# usb.net
KiCad netlist of a schematic drawn in Altium Designer
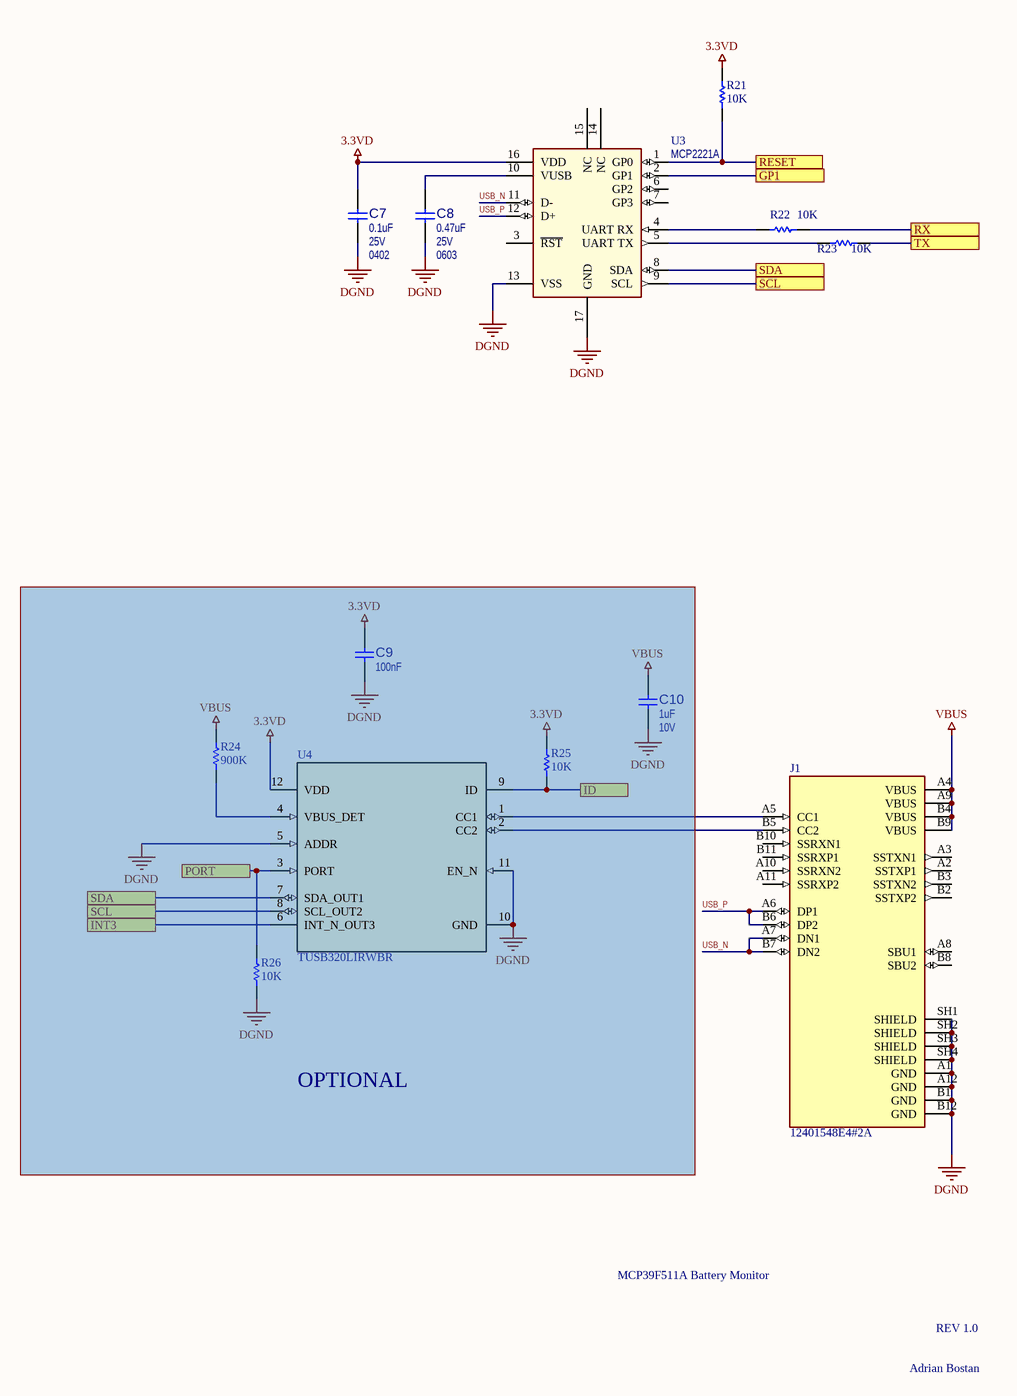
[diagram p0: usb.SchDoc]

(export (version "E")
  (design (tool "Eeschema 10.0.6"))
  (components
    (comp (ref "C7")
      (value "0.1uF")
      (footprint "CAP0603M")
      (description "Capacitor")
      (fields
        (field (name "VOLTAGE") "25V")
        (field (name "PACKAGE") "0402")
        (field (name "TOLERANCE") "10%")
        (field (name "OWNER") "Randolph Sobrepena")
      )
      (libsource (lib "MCHP-CDB") (part "Capacitor NP"))
    )
    (comp (ref "C8")
      (value "0.47uF")
      (footprint "CAP0603M")
      (description "Capacitor")
      (fields
        (field (name "VOLTAGE") "25V")
        (field (name "PACKAGE") "0603")
        (field (name "TOLERANCE") "10%")
        (field (name "OWNER") "Tad Ahlvers")
      )
      (libsource (lib "MCHP-CDB") (part "Capacitor NP"))
    )
    (comp (ref "C9")
      (value "100nF")
      (footprint "CAP0603M")
      (description "Capacitor")
      (fields (field (name "TOLERANCE") "10%") (field (name "OWNER") "Aaron VanDuerm"))
      (libsource (lib "MCHP-CDB") (part "Capacitor NP"))
    )
    (comp (ref "C10")
      (value "1uF")
      (footprint "CAP0603M")
      (description "Capacitor")
      (fields
        (field (name "VOLTAGE") "10V")
        (field (name "TOLERANCE") "10%")
        (field (name "OWNER") "Aaron VanDuerm")
      )
      (libsource (lib "MCHP-CDB") (part "Capacitor NP"))
    )
    (comp (ref "J1")
      (value "12401548E4#2A")
      (footprint "12401548E4#2A")
      (fields (field (name "MF") "Amphenol ICC"))
      (libsource (lib "12401548E4_2A") (part "12401548E4#2A"))
    )
    (comp (ref "R21")
      (value "10K")
      (footprint "RES0603M")
      (description "Resistor")
      (fields (field (name "Comment") "Res1") (field (name "PUBLISHER") "Altium Limited"))
      (libsource (lib "Miscellaneous Devices") (part "Res1"))
    )
    (comp (ref "R22")
      (value "10K")
      (footprint "RES0603M")
      (description "Resistor")
      (fields (field (name "Comment") "Res1") (field (name "PUBLISHER") "Altium Limited"))
      (libsource (lib "Miscellaneous Devices") (part "Res1"))
    )
    (comp (ref "R23")
      (value "10K")
      (footprint "RES0603M")
      (description "Resistor")
      (fields (field (name "Comment") "Res1") (field (name "PUBLISHER") "Altium Limited"))
      (libsource (lib "Miscellaneous Devices") (part "Res1"))
    )
    (comp (ref "R24")
      (value "900K")
      (footprint "RES0603M")
      (description "Resistor")
      (fields (field (name "Comment") "Res1") (field (name "PUBLISHER") "Altium Limited"))
      (libsource (lib "Miscellaneous Devices") (part "Res1"))
    )
    (comp (ref "R25")
      (value "10K")
      (footprint "RES0603M")
      (description "Resistor")
      (fields (field (name "Comment") "Res1") (field (name "PUBLISHER") "Altium Limited"))
      (libsource (lib "Miscellaneous Devices") (part "Res1"))
    )
    (comp (ref "R26")
      (value "10K")
      (footprint "RES0603M")
      (description "Resistor")
      (fields (field (name "Comment") "Res1") (field (name "PUBLISHER") "Altium Limited"))
      (libsource (lib "Miscellaneous Devices") (part "Res1"))
    )
    (comp (ref "U3")
      (value "MCP2221A")
      (footprint "QFN65P400X400X95-17N")
      (fields (field (name "Comment") "MCP2221") (field (name "OWNER") "Tim Moffat"))
      (libsource (lib "MCP2221A") (part "MCP2221"))
    )
    (comp (ref "U4")
      (value "TUSB320LIRWBR")
      (footprint "12-x2qfn")
      (description "Imported")
      (fields (field (name "MANUFACTURER") "Texas Instruments"))
      (libsource (lib "2020-03-31_01-35-02") (part "TUSB320LIRWBR"))
    )
  )
  (nets
    (net (code "1") (name "/GP1") (class "Default")
      (node (ref "U3") (pin "2") (pinfunction "GP1_2") (pintype "bidirectional"))
    )
    (net (code "2") (name "/ID") (class "Default")
      (node (ref "R25") (pin "1") (pinfunction "1_1") (pintype "passive"))
      (node (ref "U4") (pin "9") (pinfunction "ID_9") (pintype "open_collector"))
    )
    (net (code "3") (name "/INT3") (class "Default")
      (node (ref "U4") (pin "6") (pinfunction "INT_N_OUT3_6") (pintype "open_collector"))
    )
    (net (code "4") (name "/PORT") (class "Default")
      (node (ref "R26") (pin "2") (pinfunction "2_2") (pintype "passive"))
      (node (ref "U4") (pin "3") (pinfunction "PORT_3") (pintype "input"))
    )
    (net (code "5") (name "/RESET") (class "Default")
      (node (ref "R21") (pin "1") (pinfunction "1_1") (pintype "passive"))
      (node (ref "U3") (pin "1") (pinfunction "GP0_1") (pintype "bidirectional"))
    )
    (net (code "6") (name "/RX") (class "Default")
      (node (ref "R22") (pin "1") (pinfunction "1_1") (pintype "passive"))
    )
    (net (code "7") (name "/SCL") (class "Default")
      (node (ref "U3") (pin "9") (pinfunction "SCL_9") (pintype "output"))
      (node (ref "U4") (pin "8") (pinfunction "SCL_OUT2_8") (pintype "bidirectional"))
    )
    (net (code "8") (name "/SDA") (class "Default")
      (node (ref "U3") (pin "8") (pinfunction "SDA_8") (pintype "bidirectional"))
      (node (ref "U4") (pin "7") (pinfunction "SDA_OUT1_7") (pintype "bidirectional"))
    )
    (net (code "9") (name "/TX") (class "Default")
      (node (ref "R23") (pin "1") (pinfunction "1_1") (pintype "passive"))
    )
    (net (code "10") (name "/USB_N") (class "Default")
      (node (ref "J1") (pin "A7") (pinfunction "DN1_A7") (pintype "bidirectional"))
      (node (ref "J1") (pin "B7") (pinfunction "DN2_B7") (pintype "bidirectional"))
      (node (ref "U3") (pin "11") (pinfunction "D-_11") (pintype "bidirectional"))
    )
    (net (code "11") (name "/USB_P") (class "Default")
      (node (ref "J1") (pin "A6") (pinfunction "DP1_A6") (pintype "bidirectional"))
      (node (ref "J1") (pin "B6") (pinfunction "DP2_B6") (pintype "bidirectional"))
      (node (ref "U3") (pin "12") (pinfunction "D+_12") (pintype "bidirectional"))
    )
    (net (code "12") (name "3.3VD") (class "Default")
      (node (ref "C7") (pin "2") (pinfunction "2_2") (pintype "passive"))
      (node (ref "C9") (pin "1") (pinfunction "1_1") (pintype "passive"))
      (node (ref "R21") (pin "2") (pinfunction "2_2") (pintype "passive"))
      (node (ref "R25") (pin "2") (pinfunction "2_2") (pintype "passive"))
      (node (ref "U3") (pin "16") (pinfunction "VDD_16") (pintype "power_in"))
      (node (ref "U4") (pin "12") (pinfunction "VDD_12") (pintype "power_in"))
    )
    (net (code "13") (name "DGND") (class "Default")
      (node (ref "C10") (pin "1") (pinfunction "1_1") (pintype "passive"))
      (node (ref "C7") (pin "1") (pinfunction "1_1") (pintype "passive"))
      (node (ref "C8") (pin "1") (pinfunction "1_1") (pintype "passive"))
      (node (ref "C9") (pin "2") (pinfunction "2_2") (pintype "passive"))
      (node (ref "J1") (pin "A1") (pinfunction "GND_A1") (pintype "power_in"))
      (node (ref "J1") (pin "A12") (pinfunction "GND_A12") (pintype "power_in"))
      (node (ref "J1") (pin "B1") (pinfunction "GND_B1") (pintype "power_in"))
      (node (ref "J1") (pin "B12") (pinfunction "GND_B12") (pintype "power_in"))
      (node (ref "J1") (pin "SH1") (pinfunction "SHIELD_SH1") (pintype "power_in"))
      (node (ref "J1") (pin "SH2") (pinfunction "SHIELD_SH2") (pintype "power_in"))
      (node (ref "J1") (pin "SH3") (pinfunction "SHIELD_SH3") (pintype "power_in"))
      (node (ref "J1") (pin "SH4") (pinfunction "SHIELD_SH4") (pintype "power_in"))
      (node (ref "R26") (pin "1") (pinfunction "1_1") (pintype "passive"))
      (node (ref "U3") (pin "13") (pinfunction "VSS_13") (pintype "power_in"))
      (node (ref "U3") (pin "17") (pinfunction "GND_17") (pintype "passive"))
      (node (ref "U4") (pin "10") (pinfunction "GND_10") (pintype "power_in"))
      (node (ref "U4") (pin "11") (pinfunction "EN_N_11") (pintype "input"))
      (node (ref "U4") (pin "5") (pinfunction "ADDR_5") (pintype "input"))
    )
    (net (code "14") (name "Net-(J1-CC1)") (class "Default")
      (node (ref "J1") (pin "A5") (pinfunction "CC1_A5") (pintype "input"))
      (node (ref "U4") (pin "1") (pinfunction "CC1_1") (pintype "bidirectional"))
    )
    (net (code "15") (name "Net-(J1-CC2)") (class "Default")
      (node (ref "J1") (pin "B5") (pinfunction "CC2_B5") (pintype "input"))
      (node (ref "U4") (pin "2") (pinfunction "CC2_2") (pintype "bidirectional"))
    )
    (net (code "16") (name "Net-(U3-UART_RX)") (class "Default")
      (node (ref "R22") (pin "2") (pinfunction "2_2") (pintype "passive"))
      (node (ref "U3") (pin "4") (pinfunction "UART_RX_4") (pintype "input"))
    )
    (net (code "17") (name "Net-(U3-UART_TX)") (class "Default")
      (node (ref "R23") (pin "2") (pinfunction "2_2") (pintype "passive"))
      (node (ref "U3") (pin "5") (pinfunction "UART_TX_5") (pintype "output"))
    )
    (net (code "18") (name "Net-(U3-VUSB)") (class "Default")
      (node (ref "C8") (pin "2") (pinfunction "2_2") (pintype "passive"))
      (node (ref "U3") (pin "10") (pinfunction "VUSB_10") (pintype "power_in"))
    )
    (net (code "19") (name "Net-(U4-VBUS_DET)") (class "Default")
      (node (ref "R24") (pin "1") (pinfunction "1_1") (pintype "passive"))
      (node (ref "U4") (pin "4") (pinfunction "VBUS_DET_4") (pintype "input"))
    )
    (net (code "20") (name "VBUS") (class "Default")
      (node (ref "C10") (pin "2") (pinfunction "2_2") (pintype "passive"))
      (node (ref "J1") (pin "A4") (pinfunction "VBUS_A4") (pintype "power_in"))
      (node (ref "J1") (pin "A9") (pinfunction "VBUS_A9") (pintype "power_in"))
      (node (ref "J1") (pin "B4") (pinfunction "VBUS_B4") (pintype "power_in"))
      (node (ref "J1") (pin "B9") (pinfunction "VBUS_B9") (pintype "power_in"))
      (node (ref "R24") (pin "2") (pinfunction "2_2") (pintype "passive"))
    )
    (net (code "21") (name "unconnected-(J1-SBU1-PadA8)") (class "Default")
      (node (ref "J1") (pin "A8") (pinfunction "SBU1_A8") (pintype "bidirectional"))
    )
    (net (code "22") (name "unconnected-(J1-SBU2-PadB8)") (class "Default")
      (node (ref "J1") (pin "B8") (pinfunction "SBU2_B8") (pintype "bidirectional"))
    )
    (net (code "23") (name "unconnected-(J1-SSRXN1-PadB10)") (class "Default")
      (node (ref "J1") (pin "B10") (pinfunction "SSRXN1_B10") (pintype "input"))
    )
    (net (code "24") (name "unconnected-(J1-SSRXN2-PadA10)") (class "Default")
      (node (ref "J1") (pin "A10") (pinfunction "SSRXN2_A10") (pintype "input"))
    )
    (net (code "25") (name "unconnected-(J1-SSRXP1-PadB11)") (class "Default")
      (node (ref "J1") (pin "B11") (pinfunction "SSRXP1_B11") (pintype "input"))
    )
    (net (code "26") (name "unconnected-(J1-SSRXP2-PadA11)") (class "Default")
      (node (ref "J1") (pin "A11") (pinfunction "SSRXP2_A11") (pintype "input"))
    )
    (net (code "27") (name "unconnected-(J1-SSTXN1-PadA3)") (class "Default")
      (node (ref "J1") (pin "A3") (pinfunction "SSTXN1_A3") (pintype "output"))
    )
    (net (code "28") (name "unconnected-(J1-SSTXN2-PadB3)") (class "Default")
      (node (ref "J1") (pin "B3") (pinfunction "SSTXN2_B3") (pintype "output"))
    )
    (net (code "29") (name "unconnected-(J1-SSTXP1-PadA2)") (class "Default")
      (node (ref "J1") (pin "A2") (pinfunction "SSTXP1_A2") (pintype "output"))
    )
    (net (code "30") (name "unconnected-(J1-SSTXP2-PadB2)") (class "Default")
      (node (ref "J1") (pin "B2") (pinfunction "SSTXP2_B2") (pintype "output"))
    )
    (net (code "31") (name "unconnected-(U3-GP2-Pad6)") (class "Default")
      (node (ref "U3") (pin "6") (pinfunction "GP2_6") (pintype "bidirectional"))
    )
    (net (code "32") (name "unconnected-(U3-GP3-Pad7)") (class "Default")
      (node (ref "U3") (pin "7") (pinfunction "GP3_7") (pintype "bidirectional"))
    )
    (net (code "33") (name "unconnected-(U3-NC-Pad14)") (class "Default")
      (node (ref "U3") (pin "14") (pinfunction "NC_14") (pintype "passive"))
    )
    (net (code "34") (name "unconnected-(U3-NC-Pad15)") (class "Default")
      (node (ref "U3") (pin "15") (pinfunction "NC_15") (pintype "passive"))
    )
    (net (code "35") (name "unconnected-(U3-~{RST}-Pad3)") (class "Default")
      (node (ref "U3") (pin "3") (pinfunction "~{RST}_3") (pintype "passive"))
    )
  )
)
